# b2b_connector.net
KiCad netlist of a schematic drawn in Altium Designer
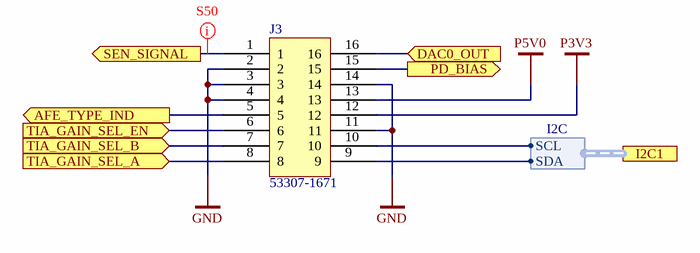
[diagram p0: b2b_connector.SchDoc]

(export (version "E")
  (design (tool "Eeschema 10.0.6"))
  (components
    (comp (ref "J3")
      (value "53307-1671")
      (footprint "533071671")
      (fields (field (name "MANUFACTURER") "Molex"))
      (libsource (lib "DiPho_lib") (part "53307-1671"))
    )
  )
  (nets
    (net (code "2") (name "/AFE_TYPE_IND") (class "Default")
      (node (ref "J3") (pin "5") (pinfunction "5_5") (pintype "passive"))
    )
    (net (code "3") (name "/DAC0_OUT") (class "Default")
      (node (ref "J3") (pin "16") (pinfunction "16_16") (pintype "passive"))
    )
    (net (code "4") (name "/PD_BIAS") (class "Default")
      (node (ref "J3") (pin "15") (pinfunction "15_15") (pintype "passive"))
    )
    (net (code "5") (name "/SCL") (class "Default")
      (node (ref "J3") (pin "10") (pinfunction "10_10") (pintype "passive"))
    )
    (net (code "6") (name "/SDA") (class "Default")
      (node (ref "J3") (pin "9") (pinfunction "9_9") (pintype "passive"))
    )
    (net (code "7") (name "/SEN_SIGNAL") (class "Default")
      (node (ref "J3") (pin "1") (pinfunction "1_1") (pintype "passive"))
    )
    (net (code "8") (name "/TIA_GAIN_SEL_A") (class "Default")
      (node (ref "J3") (pin "8") (pinfunction "8_8") (pintype "passive"))
    )
    (net (code "9") (name "/TIA_GAIN_SEL_B") (class "Default")
      (node (ref "J3") (pin "7") (pinfunction "7_7") (pintype "passive"))
    )
    (net (code "10") (name "/TIA_GAIN_SEL_EN") (class "Default")
      (node (ref "J3") (pin "6") (pinfunction "6_6") (pintype "passive"))
    )
    (net (code "12") (name "GND") (class "Default")
      (node (ref "J3") (pin "11") (pinfunction "11_11") (pintype "passive"))
      (node (ref "J3") (pin "14") (pinfunction "14_14") (pintype "passive"))
      (node (ref "J3") (pin "2") (pinfunction "2_2") (pintype "passive"))
      (node (ref "J3") (pin "3") (pinfunction "3_3") (pintype "passive"))
      (node (ref "J3") (pin "4") (pinfunction "4_4") (pintype "passive"))
    )
    (net (code "13") (name "P3V3") (class "Default")
      (node (ref "J3") (pin "12") (pinfunction "12_12") (pintype "passive"))
    )
    (net (code "14") (name "P5V0") (class "Default")
      (node (ref "J3") (pin "13") (pinfunction "13_13") (pintype "passive"))
    )
  )
)
